# Connectors.net
KiCad netlist of a schematic drawn in Altium Designer
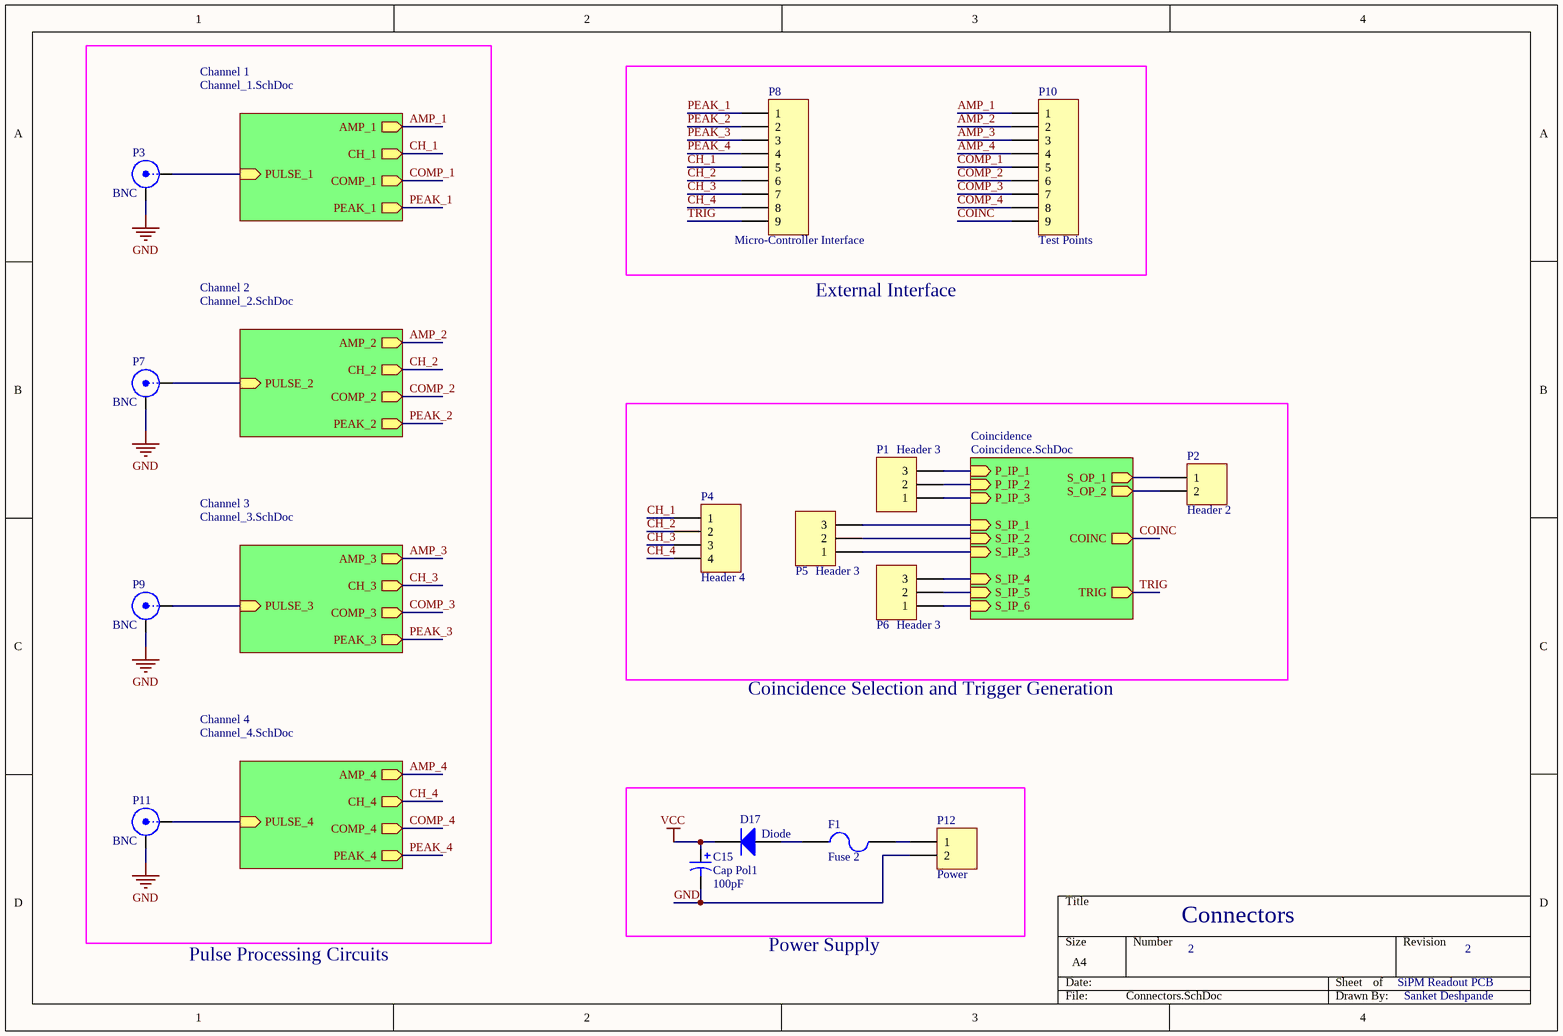
[diagram p0: Connectors.SchDoc]

(export (version "E")
  (design (tool "Eeschema 10.0.6"))
  (components
    (comp (ref "C15")
      (value "Cap Pol1")
      (footprint "RB7.6-15")
      (description "Polarized Capacitor (Radial)")
      (fields (field (name "ALTIUM_VALUE") "100pF") (field (name "PUBLISHER") "Altium Limited"))
      (libsource (lib "Miscellaneous Devices") (part "Cap Pol1"))
    )
    (comp (ref "D17")
      (value "Diode")
      (footprint "SMC")
      (description "Default Diode")
      (fields (field (name "PUBLISHER") "Altium Limited"))
      (libsource (lib "Miscellaneous Devices") (part "Diode"))
    )
    (comp (ref "F1")
      (value "Fuse 2")
      (footprint "PIN-W2/E2.8")
      (description "Fuse")
      (fields (field (name "PUBLISHER") "Altium Limited"))
      (libsource (lib "Miscellaneous Devices") (part "Fuse 2"))
    )
    (comp (ref "P1")
      (value "Header 3")
      (footprint "HDR1X3")
      (description "Header, 3-Pin")
      (fields (field (name "PUBLISHER") "Altium Limited"))
      (libsource (lib "Miscellaneous Connectors") (part "Header 3"))
    )
    (comp (ref "P2")
      (value "Header 2")
      (footprint "HDR1X2")
      (description "Header, 2-Pin")
      (fields (field (name "PUBLISHER") "Altium Limited"))
      (libsource (lib "Miscellaneous Connectors") (part "Header 2"))
    )
    (comp (ref "P3")
      (value "BNC")
      (footprint "BNC_RA CON")
      (description "BNC Elbow Connector")
      (fields (field (name "PUBLISHER") "Altium Limited"))
      (libsource (lib "Miscellaneous Connectors") (part "BNC"))
    )
    (comp (ref "P4")
      (value "Header 4")
      (footprint "HDR1X4")
      (description "Header, 4-Pin")
      (fields (field (name "PUBLISHER") "Altium Limited"))
      (libsource (lib "Miscellaneous Connectors") (part "Header 4"))
    )
    (comp (ref "P5")
      (value "Header 3")
      (footprint "HDR1X3")
      (description "Header, 3-Pin")
      (fields (field (name "PUBLISHER") "Altium Limited"))
      (libsource (lib "Miscellaneous Connectors") (part "Header 3"))
    )
    (comp (ref "P6")
      (value "Header 3")
      (footprint "HDR1X3")
      (description "Header, 3-Pin")
      (fields (field (name "PUBLISHER") "Altium Limited"))
      (libsource (lib "Miscellaneous Connectors") (part "Header 3"))
    )
    (comp (ref "P7")
      (value "BNC")
      (footprint "BNC_RA CON")
      (description "BNC Elbow Connector")
      (fields (field (name "PUBLISHER") "Altium Limited"))
      (libsource (lib "Miscellaneous Connectors") (part "BNC"))
    )
    (comp (ref "P8")
      (value "Micro-Controller Interface")
      (footprint "HDR1X9")
      (description "Header, 9-Pin")
      (fields (field (name "PUBLISHER") "Altium Limited"))
      (libsource (lib "Miscellaneous Connectors") (part "Header 9"))
    )
    (comp (ref "P9")
      (value "BNC")
      (footprint "BNC_RA CON")
      (description "BNC Elbow Connector")
      (fields (field (name "PUBLISHER") "Altium Limited"))
      (libsource (lib "Miscellaneous Connectors") (part "BNC"))
    )
    (comp (ref "P10")
      (value "Test Points")
      (footprint "HDR1X9")
      (description "Header, 9-Pin")
      (fields (field (name "PUBLISHER") "Altium Limited"))
      (libsource (lib "Miscellaneous Connectors") (part "Header 9"))
    )
    (comp (ref "P11")
      (value "BNC")
      (footprint "BNC_RA CON")
      (description "BNC Elbow Connector")
      (fields (field (name "PUBLISHER") "Altium Limited"))
      (libsource (lib "Miscellaneous Connectors") (part "BNC"))
    )
    (comp (ref "P12")
      (value "Power")
      (footprint "HDR1X2")
      (description "Header, 2-Pin")
      (fields (field (name "PUBLISHER") "Altium Limited"))
      (libsource (lib "Miscellaneous Connectors") (part "Header 2"))
    )
  )
  (nets
    (net (code "1") (name "/AMP_1") (class "Default")
      (node (ref "P10") (pin "1") (pinfunction "1_1") (pintype "passive"))
    )
    (net (code "2") (name "/AMP_2") (class "Default")
      (node (ref "P10") (pin "2") (pinfunction "2_2") (pintype "passive"))
    )
    (net (code "3") (name "/AMP_3") (class "Default")
      (node (ref "P10") (pin "3") (pinfunction "3_3") (pintype "passive"))
    )
    (net (code "4") (name "/AMP_4") (class "Default")
      (node (ref "P10") (pin "4") (pinfunction "4_4") (pintype "passive"))
    )
    (net (code "5") (name "/CH_1") (class "Default")
      (node (ref "P4") (pin "1") (pinfunction "1_1") (pintype "passive"))
      (node (ref "P8") (pin "5") (pinfunction "5_5") (pintype "passive"))
    )
    (net (code "6") (name "/CH_2") (class "Default")
      (node (ref "P4") (pin "2") (pinfunction "2_2") (pintype "passive"))
      (node (ref "P8") (pin "6") (pinfunction "6_6") (pintype "passive"))
    )
    (net (code "7") (name "/CH_3") (class "Default")
      (node (ref "P4") (pin "3") (pinfunction "3_3") (pintype "passive"))
      (node (ref "P8") (pin "7") (pinfunction "7_7") (pintype "passive"))
    )
    (net (code "8") (name "/CH_4") (class "Default")
      (node (ref "P4") (pin "4") (pinfunction "4_4") (pintype "passive"))
      (node (ref "P8") (pin "8") (pinfunction "8_8") (pintype "passive"))
    )
    (net (code "9") (name "/COINC") (class "Default")
      (node (ref "P10") (pin "9") (pinfunction "9_9") (pintype "passive"))
    )
    (net (code "10") (name "/COMP_1") (class "Default")
      (node (ref "P10") (pin "5") (pinfunction "5_5") (pintype "passive"))
    )
    (net (code "11") (name "/COMP_2") (class "Default")
      (node (ref "P10") (pin "6") (pinfunction "6_6") (pintype "passive"))
    )
    (net (code "12") (name "/COMP_3") (class "Default")
      (node (ref "P10") (pin "7") (pinfunction "7_7") (pintype "passive"))
    )
    (net (code "13") (name "/COMP_4") (class "Default")
      (node (ref "P10") (pin "8") (pinfunction "8_8") (pintype "passive"))
    )
    (net (code "14") (name "/PEAK_1") (class "Default")
      (node (ref "P8") (pin "1") (pinfunction "1_1") (pintype "passive"))
    )
    (net (code "15") (name "/PEAK_2") (class "Default")
      (node (ref "P8") (pin "2") (pinfunction "2_2") (pintype "passive"))
    )
    (net (code "16") (name "/PEAK_3") (class "Default")
      (node (ref "P8") (pin "3") (pinfunction "3_3") (pintype "passive"))
    )
    (net (code "17") (name "/PEAK_4") (class "Default")
      (node (ref "P8") (pin "4") (pinfunction "4_4") (pintype "passive"))
    )
    (net (code "18") (name "/PULSE_1") (class "Default")
      (node (ref "P3") (pin "1") (pinfunction "X_1") (pintype "passive"))
    )
    (net (code "19") (name "/PULSE_2") (class "Default")
      (node (ref "P7") (pin "1") (pinfunction "X_1") (pintype "passive"))
    )
    (net (code "20") (name "/PULSE_3") (class "Default")
      (node (ref "P9") (pin "1") (pinfunction "X_1") (pintype "passive"))
    )
    (net (code "21") (name "/PULSE_4") (class "Default")
      (node (ref "P11") (pin "1") (pinfunction "X_1") (pintype "passive"))
    )
    (net (code "22") (name "/P_IP_1") (class "Default")
      (node (ref "P1") (pin "3") (pinfunction "3_3") (pintype "passive"))
    )
    (net (code "23") (name "/P_IP_2") (class "Default")
      (node (ref "P1") (pin "2") (pinfunction "2_2") (pintype "passive"))
    )
    (net (code "24") (name "/P_IP_3") (class "Default")
      (node (ref "P1") (pin "1") (pinfunction "1_1") (pintype "passive"))
    )
    (net (code "25") (name "/S_IP_1") (class "Default")
      (node (ref "P5") (pin "3") (pinfunction "3_3") (pintype "passive"))
    )
    (net (code "26") (name "/S_IP_2") (class "Default")
      (node (ref "P5") (pin "2") (pinfunction "2_2") (pintype "passive"))
    )
    (net (code "27") (name "/S_IP_3") (class "Default")
      (node (ref "P5") (pin "1") (pinfunction "1_1") (pintype "passive"))
    )
    (net (code "28") (name "/S_IP_4") (class "Default")
      (node (ref "P6") (pin "3") (pinfunction "3_3") (pintype "passive"))
    )
    (net (code "29") (name "/S_IP_5") (class "Default")
      (node (ref "P6") (pin "2") (pinfunction "2_2") (pintype "passive"))
    )
    (net (code "30") (name "/S_IP_6") (class "Default")
      (node (ref "P6") (pin "1") (pinfunction "1_1") (pintype "passive"))
    )
    (net (code "31") (name "/S_OP_1") (class "Default")
      (node (ref "P2") (pin "1") (pinfunction "1_1") (pintype "passive"))
    )
    (net (code "32") (name "/S_OP_2") (class "Default")
      (node (ref "P2") (pin "2") (pinfunction "2_2") (pintype "passive"))
    )
    (net (code "33") (name "/TRIG") (class "Default")
      (node (ref "P8") (pin "9") (pinfunction "9_9") (pintype "passive"))
    )
    (net (code "34") (name "GND") (class "Default")
      (node (ref "C15") (pin "2") (pinfunction "2_2") (pintype "passive"))
      (node (ref "P11") (pin "2") (pinfunction "Y_2") (pintype "passive"))
      (node (ref "P12") (pin "2") (pinfunction "2_2") (pintype "passive"))
      (node (ref "P3") (pin "2") (pinfunction "Y_2") (pintype "passive"))
      (node (ref "P7") (pin "2") (pinfunction "Y_2") (pintype "passive"))
      (node (ref "P9") (pin "2") (pinfunction "Y_2") (pintype "passive"))
    )
    (net (code "35") (name "Net-(D17-A)") (class "Default")
      (node (ref "D17") (pin "1") (pinfunction "A_1") (pintype "passive"))
      (node (ref "F1") (pin "1") (pinfunction "1_1") (pintype "passive"))
    )
    (net (code "36") (name "Net-(F1-Pad2)") (class "Default")
      (node (ref "F1") (pin "2") (pinfunction "2_2") (pintype "passive"))
      (node (ref "P12") (pin "1") (pinfunction "1_1") (pintype "passive"))
    )
    (net (code "37") (name "VCC") (class "Default")
      (node (ref "C15") (pin "1") (pinfunction "1_1") (pintype "passive"))
      (node (ref "D17") (pin "2") (pinfunction "K_2") (pintype "passive"))
    )
  )
)
